# CUVET_DECTECT_POWER.net
KiCad netlist of a schematic drawn in Altium Designer
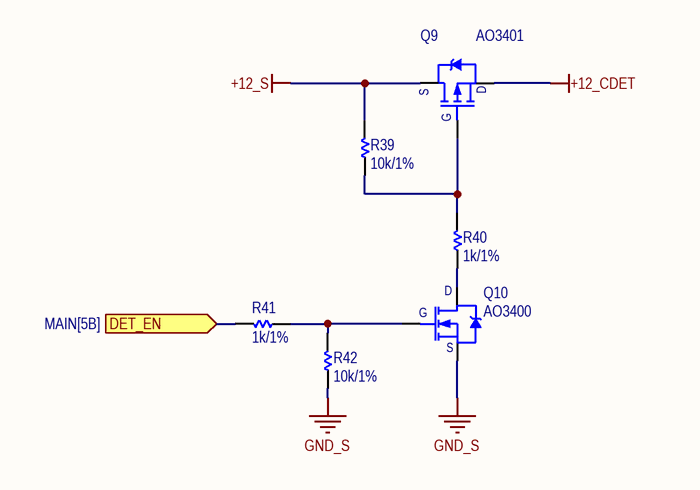
[diagram p0: CUVET_DECTECT_POWER.SchDoc]

(export (version "E")
  (design (tool "Eeschema 10.0.6"))
  (components
    (comp (ref "Q9")
      (value "AO3401")
      (footprint "SOT23-123")
      (description "P-MOS 30V 4A")
      (libsource (lib "Library") (part "AO3401"))
    )
    (comp (ref "Q10")
      (value "AO3400")
      (footprint "SOT23-123")
      (description "N-MOS 30V 5.8A")
      (libsource (lib "Library") (part "AO3400"))
    )
    (comp (ref "R39")
      (value "10k/1%")
      (footprint "RES-SMD-0603")
      (description "ERJ-3EKF1002V")
      (fields
        (field (name "MANUFACTURER") "Generic Components")
        (field (name "PUBLISHER") "Altium Hobart Technology Centre")
      )
      (libsource (lib "Library") (part "Res-SMD"))
    )
    (comp (ref "R40")
      (value "1k/1%")
      (footprint "RES-SMD-0603")
      (description "ERJ-3EKF1001V")
      (fields
        (field (name "MANUFACTURER") "Generic Components")
        (field (name "PUBLISHER") "Altium Hobart Technology Centre")
      )
      (libsource (lib "Library") (part "Res-SMD"))
    )
    (comp (ref "R41")
      (value "1k/1%")
      (footprint "RES-SMD-0603")
      (description "ERJ-3EKF1001V")
      (fields
        (field (name "MANUFACTURER") "Generic Components")
        (field (name "PUBLISHER") "Altium Hobart Technology Centre")
      )
      (libsource (lib "Library") (part "Res-SMD"))
    )
    (comp (ref "R42")
      (value "10k/1%")
      (footprint "RES-SMD-0603")
      (description "ERJ-3EKF1002V")
      (fields
        (field (name "MANUFACTURER") "Generic Components")
        (field (name "PUBLISHER") "Altium Hobart Technology Centre")
      )
      (libsource (lib "Library") (part "Res-SMD"))
    )
  )
  (nets
    (net (code "1") (name "+12_CDET") (class "Default")
      (node (ref "Q9") (pin "2") (pinfunction "D_2") (pintype "passive"))
    )
    (net (code "2") (name "+12_S") (class "Default")
      (node (ref "Q9") (pin "3") (pinfunction "S_3") (pintype "passive"))
      (node (ref "R39") (pin "1") (pinfunction "1_1") (pintype "passive"))
    )
    (net (code "3") (name "/DET_EN") (class "Default")
      (node (ref "R41") (pin "1") (pinfunction "1_1") (pintype "passive"))
    )
    (net (code "4") (name "GND_S") (class "Default")
      (node (ref "Q10") (pin "3") (pinfunction "S_3") (pintype "passive"))
      (node (ref "R42") (pin "2") (pinfunction "2_2") (pintype "passive"))
    )
    (net (code "5") (name "Net-(Q9-G)") (class "Default")
      (node (ref "Q9") (pin "1") (pinfunction "G_1") (pintype "passive"))
      (node (ref "R39") (pin "2") (pinfunction "2_2") (pintype "passive"))
      (node (ref "R40") (pin "1") (pinfunction "1_1") (pintype "passive"))
    )
    (net (code "6") (name "Net-(Q10-D)") (class "Default")
      (node (ref "Q10") (pin "2") (pinfunction "D_2") (pintype "passive"))
      (node (ref "R40") (pin "2") (pinfunction "2_2") (pintype "passive"))
    )
    (net (code "7") (name "Net-(Q10-G)") (class "Default")
      (node (ref "Q10") (pin "1") (pinfunction "G_1") (pintype "passive"))
      (node (ref "R41") (pin "2") (pinfunction "2_2") (pintype "passive"))
      (node (ref "R42") (pin "1") (pinfunction "1_1") (pintype "passive"))
    )
  )
)
